# POWERAMP.net
KiCad netlist of a schematic drawn in Altium Designer
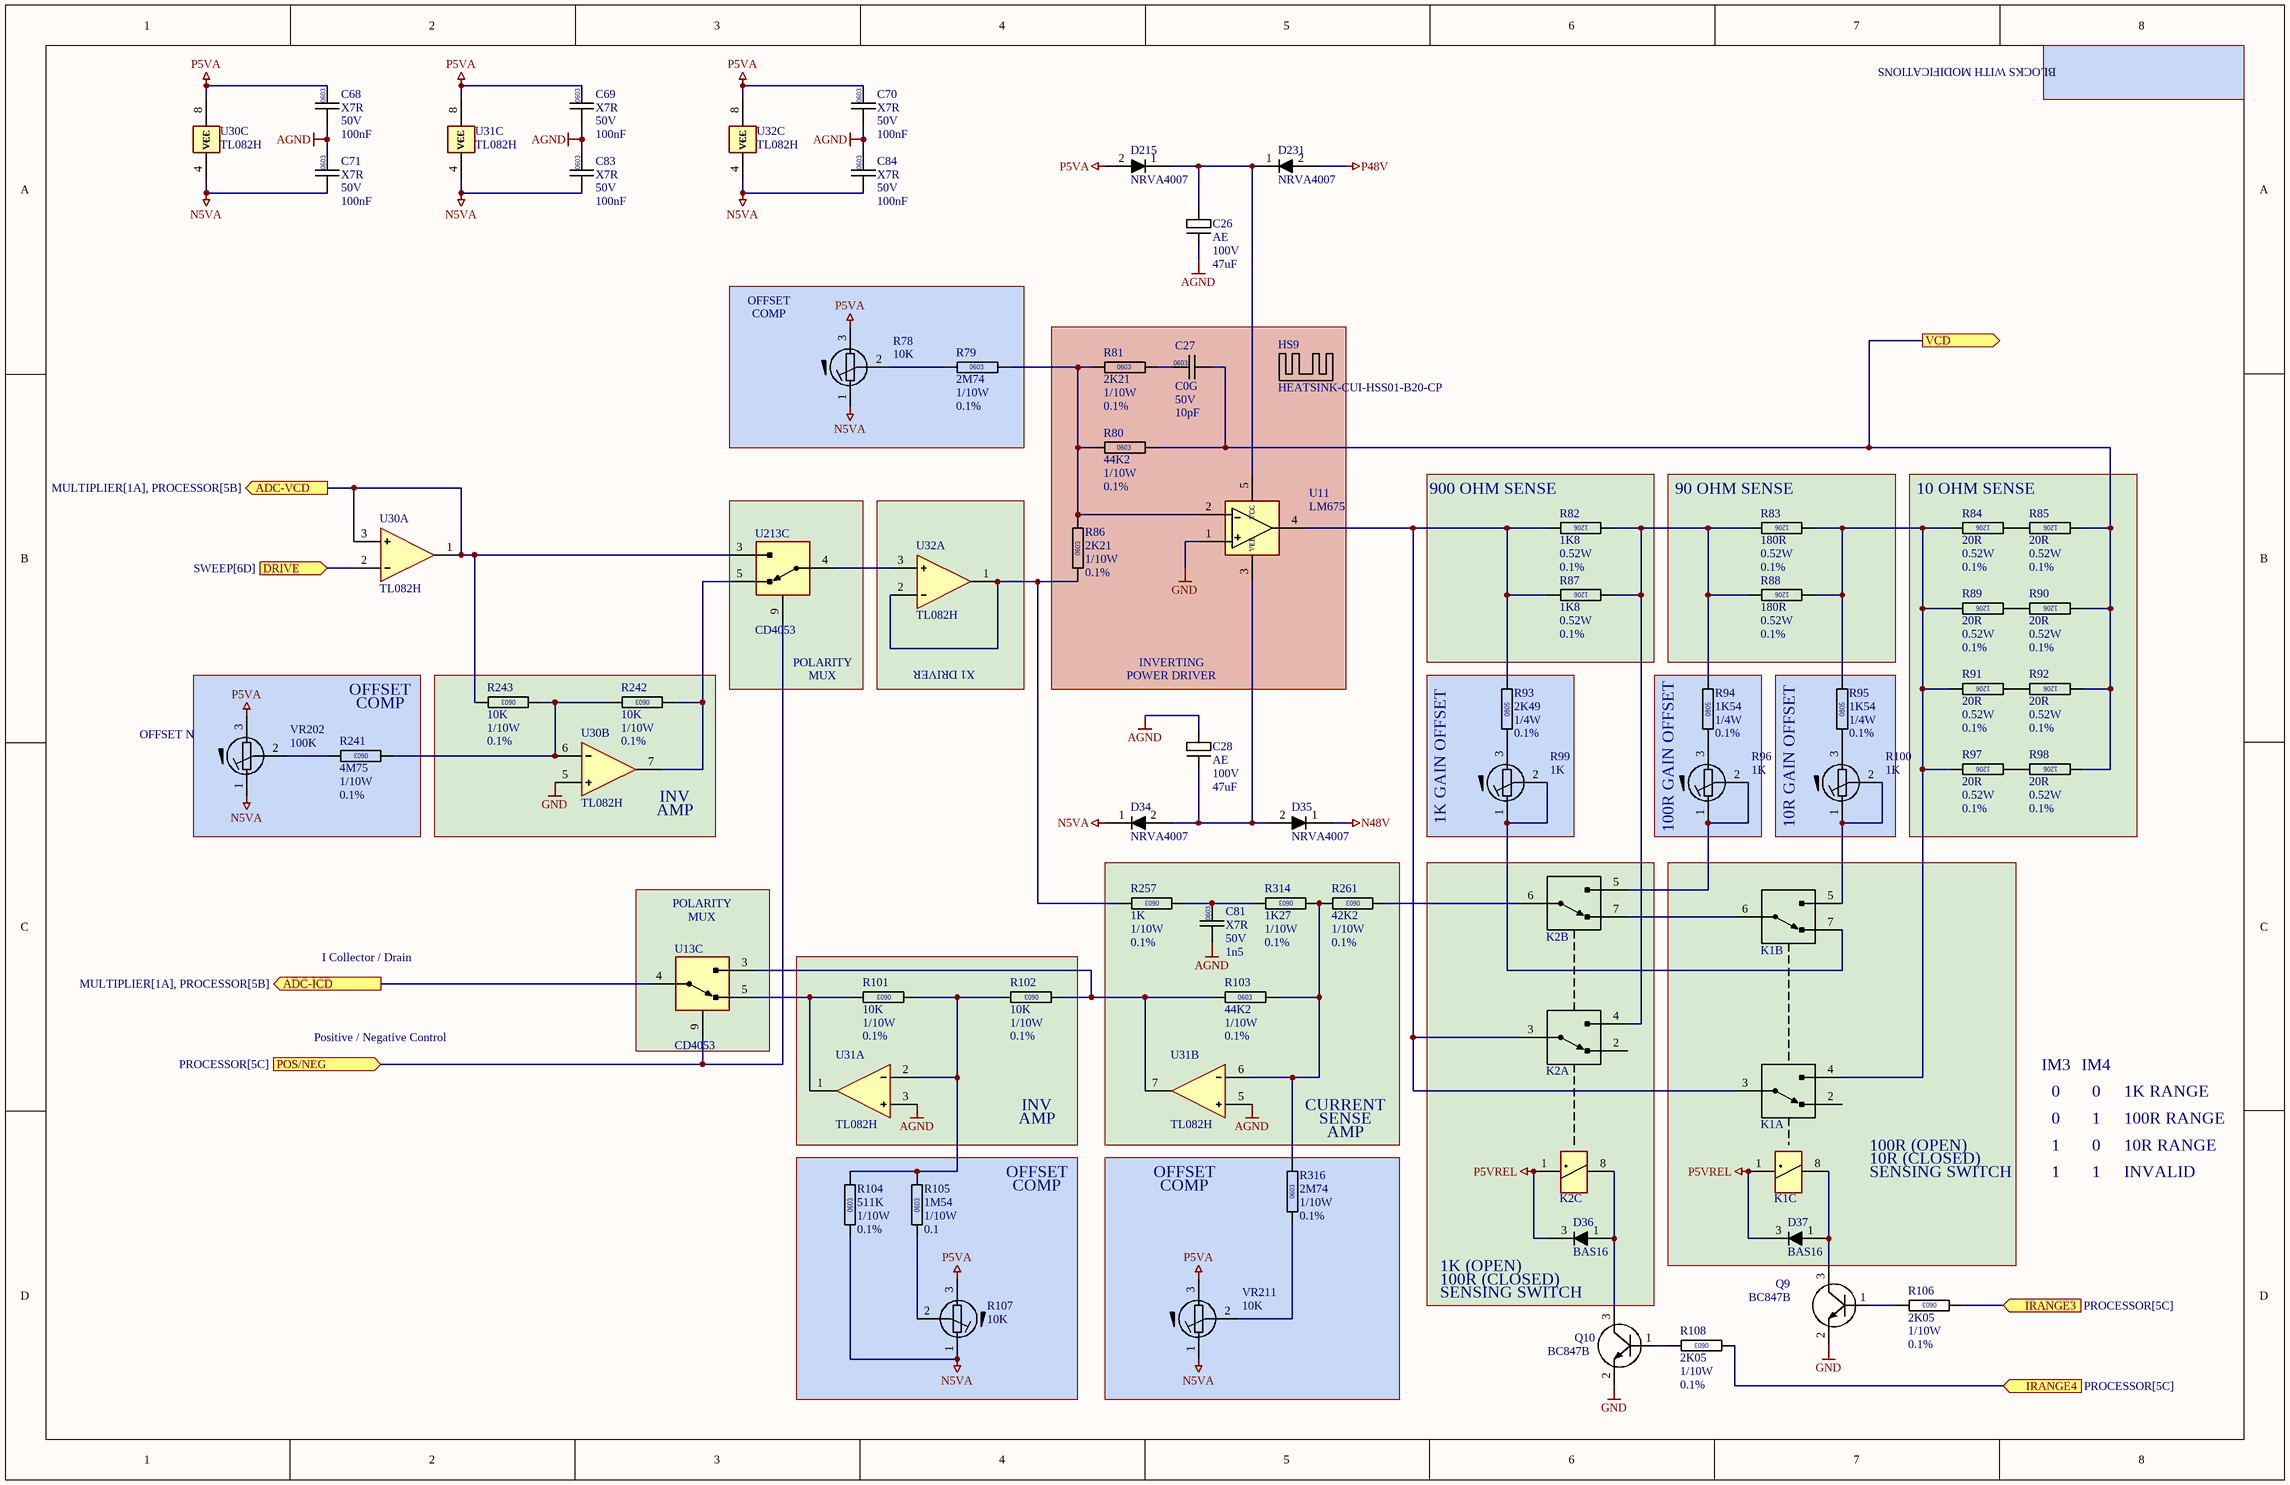
[diagram p0: POWERAMP.SchDoc]

(export (version "E")
  (design (tool "Eeschema 10.0.6"))
  (components
    (comp (ref "C26")
      (value "CAP0603")
      (footprint "CAPAE-KEMET-ESL476M100AH9AA")
      (description "CAPACITOR,ALU,47uF,100V,TH,P5mm,D10mm,H14mm")
      (fields
        (field (name "DIELECTRIC") "AE")
        (field (name "VOLTAGE") "100V")
        (field (name "CAPACITANCE") "47uF")
      )
      (libsource (lib "CAPACITORS") (part "CAPP-AE-47uF-100V-TH050P100D140H"))
    )
    (comp (ref "C27")
      (value "CAP0603")
      (footprint "CAPC0603")
      (description "CAPACITOR,CERAMIC,10pF,50V,C0G,0603")
      (fields
        (field (name "DIELECTRIC") "C0G")
        (field (name "VOLTAGE") "50V")
        (field (name "CAPACITANCE") "10pF")
      )
      (libsource (lib "CAPACITORS") (part "CAPC-0603-10PF-50V-C0G"))
    )
    (comp (ref "C28")
      (value "CAP0603")
      (footprint "CAPAE-KEMET-ESL476M100AH9AA")
      (description "CAPACITOR,ALU,47uF,100V,TH,P5mm,D10mm,H14mm")
      (fields
        (field (name "DIELECTRIC") "AE")
        (field (name "VOLTAGE") "100V")
        (field (name "CAPACITANCE") "47uF")
      )
      (libsource (lib "CAPACITORS") (part "CAPP-AE-47uF-100V-TH050P100D140H"))
    )
    (comp (ref "C68")
      (value "CAP0603")
      (footprint "CAPC0603")
      (description "CAPACITOR,CERAMIC,100nF,50V,X7R,0603")
      (fields
        (field (name "DIELECTRIC") "X7R")
        (field (name "VOLTAGE") "50V")
        (field (name "CAPACITANCE") "100nF")
      )
      (libsource (lib "CAPACITORS") (part "CAPC-0603-100nF-50V-X7R"))
    )
    (comp (ref "C69")
      (value "CAP0603")
      (footprint "CAPC0603")
      (description "CAPACITOR,CERAMIC,100nF,50V,X7R,0603")
      (fields
        (field (name "DIELECTRIC") "X7R")
        (field (name "VOLTAGE") "50V")
        (field (name "CAPACITANCE") "100nF")
      )
      (libsource (lib "CAPACITORS") (part "CAPC-0603-100nF-50V-X7R"))
    )
    (comp (ref "C70")
      (value "CAP0603")
      (footprint "CAPC0603")
      (description "CAPACITOR,CERAMIC,100nF,50V,X7R,0603")
      (fields
        (field (name "DIELECTRIC") "X7R")
        (field (name "VOLTAGE") "50V")
        (field (name "CAPACITANCE") "100nF")
      )
      (libsource (lib "CAPACITORS") (part "CAPC-0603-100nF-50V-X7R"))
    )
    (comp (ref "C71")
      (value "CAP0603")
      (footprint "CAPC0603")
      (description "CAPACITOR,CERAMIC,100nF,50V,X7R,0603")
      (fields
        (field (name "DIELECTRIC") "X7R")
        (field (name "VOLTAGE") "50V")
        (field (name "CAPACITANCE") "100nF")
      )
      (libsource (lib "CAPACITORS") (part "CAPC-0603-100nF-50V-X7R"))
    )
    (comp (ref "C81")
      (value "CAP0603")
      (footprint "CAPC0603")
      (description "CAPACITOR,CERAMIC,1n5,50V,X7R,0603")
      (fields
        (field (name "DIELECTRIC") "X7R")
        (field (name "VOLTAGE") "50V")
        (field (name "CAPACITANCE") "1n5")
      )
      (libsource (lib "CAPACITORS") (part "CAPC-0603-1n5-50V-X7R"))
    )
    (comp (ref "C83")
      (value "CAP0603")
      (footprint "CAPC0603")
      (description "CAPACITOR,CERAMIC,100nF,50V,X7R,0603")
      (fields
        (field (name "DIELECTRIC") "X7R")
        (field (name "VOLTAGE") "50V")
        (field (name "CAPACITANCE") "100nF")
      )
      (libsource (lib "CAPACITORS") (part "CAPC-0603-100nF-50V-X7R"))
    )
    (comp (ref "C84")
      (value "CAP0603")
      (footprint "CAPC0603")
      (description "CAPACITOR,CERAMIC,100nF,50V,X7R,0603")
      (fields
        (field (name "DIELECTRIC") "X7R")
        (field (name "VOLTAGE") "50V")
        (field (name "CAPACITANCE") "100nF")
      )
      (libsource (lib "CAPACITORS") (part "CAPC-0603-100nF-50V-X7R"))
    )
    (comp (ref "D34")
      (value "NRVA4007")
      (footprint "DO214AC")
      (description "DIODE,RECTIFIER,1000V,1A,ONSEMI,NRVA4007,SMA")
      (libsource (lib "DIODES") (part "DIODE-ONSEMI-NRVA4007T3G"))
    )
    (comp (ref "D35")
      (value "NRVA4007")
      (footprint "DO214AC")
      (description "DIODE,RECTIFIER,1000V,1A,ONSEMI,NRVA4007,SMA")
      (libsource (lib "DIODES") (part "DIODE-ONSEMI-NRVA4007T3G"))
    )
    (comp (ref "D36")
      (value "BAS16")
      (footprint "SOT23")
      (description "DIODE,RECTIFIER,75V,0.3A,BAS16,SOT23")
      (libsource (lib "DIODES") (part "DIODE-RECTIFIER-DIODES-BAS16-SOT23"))
    )
    (comp (ref "D37")
      (value "BAS16")
      (footprint "SOT23")
      (description "DIODE,RECTIFIER,75V,0.3A,BAS16,SOT23")
      (libsource (lib "DIODES") (part "DIODE-RECTIFIER-DIODES-BAS16-SOT23"))
    )
    (comp (ref "D215")
      (value "NRVA4007")
      (footprint "DO214AC")
      (description "DIODE,RECTIFIER,1000V,1A,ONSEMI,NRVA4007,SMA")
      (libsource (lib "DIODES") (part "DIODE-ONSEMI-NRVA4007T3G"))
    )
    (comp (ref "D231")
      (value "NRVA4007")
      (footprint "DO214AC")
      (description "DIODE,RECTIFIER,1000V,1A,ONSEMI,NRVA4007,SMA")
      (libsource (lib "DIODES") (part "DIODE-ONSEMI-NRVA4007T3G"))
    )
    (comp (ref "HS9")
      (value "HEATSINK-CUI-HSS01-B20-CP")
      (footprint "HEATSINK-CUI-HSS01-B20-CP")
      (description "HEATSINKSTAMPED,CLIP-ON,BOARDMOUNT,3W,25C/W,CUI,HSS01-B20-CP")
      (libsource (lib "HEATSINK") (part "HEATSINK-CUI-HSS01-B20-CP"))
    )
    (comp (ref "K1")
      (value "RELAY-KEMET-UA2-5NJ")
      (footprint "RELAY-KEMET-UA2-5NJ")
      (description "RELAY,DPDT,1A,250VAC,220VDC,5V COIL,KEMET,UA2-5NJ")
      (libsource (lib "RELAYS") (part "RELAY-KEMET-UA2-5NJ"))
    )
    (comp (ref "K2")
      (value "RELAY-KEMET-UA2-5NJ")
      (footprint "RELAY-KEMET-UA2-5NJ")
      (description "RELAY,DPDT,1A,250VAC,220VDC,5V COIL,KEMET,UA2-5NJ")
      (libsource (lib "") (part "RELAY-KEMET-UA2-5NJ_1"))
    )
    (comp (ref "Q9")
      (value "BC847B")
      (footprint "SOT23")
      (description "XSTR,NPN,45V,0.1A,,BC847B,SOT23")
      (libsource (lib "TRANSISTORS") (part "XSTR-NPN-BC847"))
    )
    (comp (ref "Q10")
      (value "BC847B")
      (footprint "SOT23")
      (description "XSTR,NPN,45V,0.1A,,BC847B,SOT23")
      (libsource (lib "TRANSISTORS") (part "XSTR-NPN-BC847"))
    )
    (comp (ref "R78")
      (value "10K")
      (footprint "TRIMMER-BOURNS-3214X")
      (description "RESISTOR,MULTITURN,VERTICAL,5T,10K")
      (fields (field (name "Comment") "TRIMMER-BOURNS-3214X-1-103E"))
      (libsource (lib "RESISTORS") (part "TRIMMER-BOURNS-3214X-1-103E"))
    )
    (comp (ref "R79")
      (value "2M74")
      (footprint "RESC0603")
      (description "RESISTOR,2M74,0.1%,100mW,0603 (1608)")
      (fields
        (field (name "POWER") "1/10W")
        (field (name "TOLERANCE") "0.1%")
        (field (name "Comment") "RESC0603")
      )
      (libsource (lib "RESISTORS") (part "RESC-0603-2M74-0.1%-1/10W"))
    )
    (comp (ref "R80")
      (value "44K2")
      (footprint "RESC0603")
      (description "RESISTOR,44K2,0.1%,100mW,0603 (1608)")
      (fields
        (field (name "POWER") "1/10W")
        (field (name "TOLERANCE") "0.1%")
        (field (name "Comment") "RESC0603")
      )
      (libsource (lib "RESISTORS") (part "RESC-0603-44K2-0.1%-1/10W"))
    )
    (comp (ref "R81")
      (value "2K21")
      (footprint "RESC0603")
      (description "RESISTOR,2K21,0.1%,100mW,0603 (1608)")
      (fields
        (field (name "POWER") "1/10W")
        (field (name "TOLERANCE") "0.1%")
        (field (name "Comment") "RESC0603")
      )
      (libsource (lib "RESISTORS") (part "RESC-0603-2K21-0.1%-1/10W"))
    )
    (comp (ref "R82")
      (value "1K8")
      (footprint "RESC1206")
      (description "RESISTOR,1K8,1206,0.1%,520mW,1206")
      (fields
        (field (name "POWER") "0.52W")
        (field (name "TOLERANCE") "0.1%")
        (field (name "Comment") "RESC1206")
      )
      (libsource (lib "RESISTORS") (part "RESC-1206-1K8-0.1%-1/2W"))
    )
    (comp (ref "R83")
      (value "180R")
      (footprint "RESC1206")
      (description "RESISTOR,180,1206,0.1%,520mW,1206")
      (fields
        (field (name "POWER") "0.52W")
        (field (name "TOLERANCE") "0.1%")
        (field (name "Comment") "RESC1206")
      )
      (libsource (lib "RESISTORS") (part "RESC-1206-180R-0.1%-1/2W"))
    )
    (comp (ref "R84")
      (value "20R")
      (footprint "RESC1206")
      (description "RESISTOR,20R,1206,0.1%,520mW,1206")
      (fields
        (field (name "POWER") "0.52W")
        (field (name "TOLERANCE") "0.1%")
        (field (name "Comment") "RESC1206")
      )
      (libsource (lib "RESISTORS") (part "RESC-1206-20R-0.1%-1/2W"))
    )
    (comp (ref "R85")
      (value "20R")
      (footprint "RESC1206")
      (description "RESISTOR,20R,1206,0.1%,520mW,1206")
      (fields
        (field (name "POWER") "0.52W")
        (field (name "TOLERANCE") "0.1%")
        (field (name "Comment") "RESC1206")
      )
      (libsource (lib "RESISTORS") (part "RESC-1206-20R-0.1%-1/2W"))
    )
    (comp (ref "R86")
      (value "2K21")
      (footprint "RESC0603")
      (description "RESISTOR,2K21,0.1%,100mW,0603 (1608)")
      (fields
        (field (name "POWER") "1/10W")
        (field (name "TOLERANCE") "0.1%")
        (field (name "Comment") "RESC0603")
      )
      (libsource (lib "RESISTORS") (part "RESC-0603-2K21-0.1%-1/10W"))
    )
    (comp (ref "R87")
      (value "1K8")
      (footprint "RESC1206")
      (description "RESISTOR,1K8,1206,0.1%,520mW,1206")
      (fields
        (field (name "POWER") "0.52W")
        (field (name "TOLERANCE") "0.1%")
        (field (name "Comment") "RESC1206")
      )
      (libsource (lib "RESISTORS") (part "RESC-1206-1K8-0.1%-1/2W"))
    )
    (comp (ref "R88")
      (value "180R")
      (footprint "RESC1206")
      (description "RESISTOR,180,1206,0.1%,520mW,1206")
      (fields
        (field (name "POWER") "0.52W")
        (field (name "TOLERANCE") "0.1%")
        (field (name "Comment") "RESC1206")
      )
      (libsource (lib "RESISTORS") (part "RESC-1206-180R-0.1%-1/2W"))
    )
    (comp (ref "R89")
      (value "20R")
      (footprint "RESC1206")
      (description "RESISTOR,20R,1206,0.1%,520mW,1206")
      (fields
        (field (name "POWER") "0.52W")
        (field (name "TOLERANCE") "0.1%")
        (field (name "Comment") "RESC1206")
      )
      (libsource (lib "RESISTORS") (part "RESC-1206-20R-0.1%-1/2W"))
    )
    (comp (ref "R90")
      (value "20R")
      (footprint "RESC1206")
      (description "RESISTOR,20R,1206,0.1%,520mW,1206")
      (fields
        (field (name "POWER") "0.52W")
        (field (name "TOLERANCE") "0.1%")
        (field (name "Comment") "RESC1206")
      )
      (libsource (lib "RESISTORS") (part "RESC-1206-20R-0.1%-1/2W"))
    )
    (comp (ref "R91")
      (value "20R")
      (footprint "RESC1206")
      (description "RESISTOR,20R,1206,0.1%,520mW,1206")
      (fields
        (field (name "POWER") "0.52W")
        (field (name "TOLERANCE") "0.1%")
        (field (name "Comment") "RESC1206")
      )
      (libsource (lib "RESISTORS") (part "RESC-1206-20R-0.1%-1/2W"))
    )
    (comp (ref "R92")
      (value "20R")
      (footprint "RESC1206")
      (description "RESISTOR,20R,1206,0.1%,520mW,1206")
      (fields
        (field (name "POWER") "0.52W")
        (field (name "TOLERANCE") "0.1%")
        (field (name "Comment") "RESC1206")
      )
      (libsource (lib "RESISTORS") (part "RESC-1206-20R-0.1%-1/2W"))
    )
    (comp (ref "R93")
      (value "2K49")
      (footprint "RESC0805")
      (description "RESISTOR,2K49,0.1%,250mW,0805")
      (fields
        (field (name "POWER") "1/4W")
        (field (name "TOLERANCE") "0.1%")
        (field (name "Comment") "RESC0805")
      )
      (libsource (lib "RESISTORS") (part "RESC-0805-2K49-0.1%-1/4W"))
    )
    (comp (ref "R94")
      (value "1K54")
      (footprint "RESC0805")
      (description "RESISTOR,1K54,0.1%,250mW,0805")
      (fields
        (field (name "POWER") "1/4W")
        (field (name "TOLERANCE") "0.1%")
        (field (name "Comment") "RESC0805")
      )
      (libsource (lib "RESISTORS") (part "RESC-0805-1K54-0.1%-1/4W"))
    )
    (comp (ref "R95")
      (value "1K54")
      (footprint "RESC0805")
      (description "RESISTOR,1K54,0.1%,250mW,0805")
      (fields
        (field (name "POWER") "1/4W")
        (field (name "TOLERANCE") "0.1%")
        (field (name "Comment") "RESC0805")
      )
      (libsource (lib "RESISTORS") (part "RESC-0805-1K54-0.1%-1/4W"))
    )
    (comp (ref "R96")
      (value "1K")
      (footprint "TRIMMER-BOURNS-3214X")
      (description "RESISTOR,MULTITURN,VERTICAL,5T,1K")
      (fields (field (name "Comment") "TRIMMER-BOURNS-3214X-1-102E"))
      (libsource (lib "RESISTORS") (part "TRIMMER-BOURNS-3214X-1-102E"))
    )
    (comp (ref "R97")
      (value "20R")
      (footprint "RESC1206")
      (description "RESISTOR,20R,1206,0.1%,520mW,1206")
      (fields
        (field (name "POWER") "0.52W")
        (field (name "TOLERANCE") "0.1%")
        (field (name "Comment") "RESC1206")
      )
      (libsource (lib "RESISTORS") (part "RESC-1206-20R-0.1%-1/2W"))
    )
    (comp (ref "R98")
      (value "20R")
      (footprint "RESC1206")
      (description "RESISTOR,20R,1206,0.1%,520mW,1206")
      (fields
        (field (name "POWER") "0.52W")
        (field (name "TOLERANCE") "0.1%")
        (field (name "Comment") "RESC1206")
      )
      (libsource (lib "RESISTORS") (part "RESC-1206-20R-0.1%-1/2W"))
    )
    (comp (ref "R99")
      (value "1K")
      (footprint "TRIMMER-BOURNS-3214X")
      (description "RESISTOR,MULTITURN,VERTICAL,5T,1K")
      (fields (field (name "Comment") "TRIMMER-BOURNS-3214X-1-102E"))
      (libsource (lib "RESISTORS") (part "TRIMMER-BOURNS-3214X-1-102E"))
    )
    (comp (ref "R100")
      (value "1K")
      (footprint "TRIMMER-BOURNS-3214X")
      (description "RESISTOR,MULTITURN,VERTICAL,5T,1K")
      (fields (field (name "Comment") "TRIMMER-BOURNS-3214X-1-102E"))
      (libsource (lib "RESISTORS") (part "TRIMMER-BOURNS-3214X-1-102E"))
    )
    (comp (ref "R101")
      (value "10K")
      (footprint "RESC0603")
      (description "RESISTOR,10K,0.1%,100mW,0603 (1608)")
      (fields
        (field (name "POWER") "1/10W")
        (field (name "TOLERANCE") "0.1%")
        (field (name "Comment") "RESC0603")
      )
      (libsource (lib "RESISTORS") (part "RESC-0603-10K-0.1%-1/10W"))
    )
    (comp (ref "R102")
      (value "10K")
      (footprint "RESC0603")
      (description "RESISTOR,10K,0.1%,100mW,0603 (1608)")
      (fields
        (field (name "POWER") "1/10W")
        (field (name "TOLERANCE") "0.1%")
        (field (name "Comment") "RESC0603")
      )
      (libsource (lib "RESISTORS") (part "RESC-0603-10K-0.1%-1/10W"))
    )
    (comp (ref "R103")
      (value "44K2")
      (footprint "RESC0603")
      (description "RESISTOR,44K2,0.1%,100mW,0603 (1608)")
      (fields
        (field (name "POWER") "1/10W")
        (field (name "TOLERANCE") "0.1%")
        (field (name "Comment") "RESC0603")
      )
      (libsource (lib "RESISTORS") (part "RESC-0603-44K2-0.1%-1/10W"))
    )
    (comp (ref "R104")
      (value "511K")
      (footprint "RESC0603")
      (description "RESISTOR,511K,0.1%,100mW,0603 (1608)")
      (fields
        (field (name "POWER") "1/10W")
        (field (name "TOLERANCE") "0.1%")
        (field (name "Comment") "RESC0603")
      )
      (libsource (lib "RESISTORS") (part "RESC-0603-511K-0.1%-1/10W"))
    )
    (comp (ref "R105")
      (value "1M54")
      (footprint "RESC0603")
      (description "RESISTOR,1M54,0.1%,100mW,0603 (1608)")
      (fields
        (field (name "POWER") "1/10W")
        (field (name "TOLERANCE") "0.1")
        (field (name "Comment") "RESC0603")
      )
      (libsource (lib "RESISTORS") (part "RESC-0603-1M54-0.1%-1/10W"))
    )
    (comp (ref "R106")
      (value "2K05")
      (footprint "RESC0603")
      (description "RESISTOR,2K05,0.11%,100mW,0603 (1608)")
      (fields
        (field (name "POWER") "1/10W")
        (field (name "TOLERANCE") "0.1%")
        (field (name "Comment") "RESC0603")
      )
      (libsource (lib "RESISTORS") (part "RESC-0603-2K05-0.1%-1/10W"))
    )
    (comp (ref "R107")
      (value "10K")
      (footprint "TRIMMER-BOURNS-3214X")
      (description "RESISTOR,MULTITURN,VERTICAL,5T,10K")
      (fields (field (name "Comment") "TRIMMER-BOURNS-3214X-1-103E"))
      (libsource (lib "RESISTORS") (part "TRIMMER-BOURNS-3214X-1-103E"))
    )
    (comp (ref "R108")
      (value "2K05")
      (footprint "RESC0603")
      (description "RESISTOR,2K05,0.11%,100mW,0603 (1608)")
      (fields
        (field (name "POWER") "1/10W")
        (field (name "TOLERANCE") "0.1%")
        (field (name "Comment") "RESC0603")
      )
      (libsource (lib "RESISTORS") (part "RESC-0603-2K05-0.1%-1/10W"))
    )
    (comp (ref "R241")
      (value "4M75")
      (footprint "RESC0603")
      (description "RESISTOR,4M75,0.1%,100mW,0603 (1608)")
      (fields
        (field (name "POWER") "1/10W")
        (field (name "TOLERANCE") "0.1%")
        (field (name "Comment") "RESC0603")
      )
      (libsource (lib "RESISTORS") (part "RESC-0603-4M75-1%-1/10W"))
    )
    (comp (ref "R242")
      (value "10K")
      (footprint "RESC0603")
      (description "RESISTOR,10K,0.1%,100mW,0603 (1608)")
      (fields
        (field (name "POWER") "1/10W")
        (field (name "TOLERANCE") "0.1%")
        (field (name "Comment") "RESC0603")
      )
      (libsource (lib "RESISTORS") (part "RESC-0603-10K-0.1%-1/10W"))
    )
    (comp (ref "R243")
      (value "10K")
      (footprint "RESC0603")
      (description "RESISTOR,10K,0.1%,100mW,0603 (1608)")
      (fields
        (field (name "POWER") "1/10W")
        (field (name "TOLERANCE") "0.1%")
        (field (name "Comment") "RESC0603")
      )
      (libsource (lib "RESISTORS") (part "RESC-0603-10K-0.1%-1/10W"))
    )
    (comp (ref "R257")
      (value "1K")
      (footprint "RESC0603")
      (description "RESISTOR,1K,0.1%,100mW,0603 (1608)")
      (fields
        (field (name "POWER") "1/10W")
        (field (name "TOLERANCE") "0.1%")
        (field (name "Comment") "RESC0603")
      )
      (libsource (lib "RESISTORS") (part "RESC-0603-1K-0.1%-1/10W"))
    )
    (comp (ref "R261")
      (value "42K2")
      (footprint "RESC0603")
      (description "RESISTOR,42K2,0.1%,100mW,0603 (1608)")
      (fields
        (field (name "POWER") "1/10W")
        (field (name "TOLERANCE") "0.1%")
        (field (name "Comment") "RESC0603")
      )
      (libsource (lib "RESISTORS") (part "RESC-0603-42K2-0.1%-1/10W"))
    )
    (comp (ref "R314")
      (value "1K27")
      (footprint "RESC0603")
      (description "RESISTOR,1K27,0.1%,100mW,0603 (1608)")
      (fields
        (field (name "POWER") "1/10W")
        (field (name "TOLERANCE") "0.1%")
        (field (name "Comment") "RESC0603")
      )
      (libsource (lib "RESISTORS") (part "RESC-0603-1K27-0.1%-1/10W"))
    )
    (comp (ref "R316")
      (value "2M74")
      (footprint "RESC0603")
      (description "RESISTOR,2M74,0.1%,100mW,0603 (1608)")
      (fields
        (field (name "POWER") "1/10W")
        (field (name "TOLERANCE") "0.1%")
        (field (name "Comment") "RESC0603")
      )
      (libsource (lib "RESISTORS") (part "RESC-0603-2M74-0.1%-1/10W"))
    )
    (comp (ref "U11")
      (value "LM675")
      (footprint "TO220-5-V")
      (description "IC,OPAMP,SINGLE,POWER,LM675,TO220-5")
      (libsource (lib "IC-OPAMP") (part "IC-TI-LM675-TO220-5"))
    )
    (comp (ref "U13")
      (value "CD4053")
      (footprint "SO127P600-16N")
      (description "IC,LOGIC,CMOS,4XXX,TRIPLE 2:1 MUX,SPLIT BLOCKS")
      (libsource (lib "IC-4XXX") (part "IC-TI-CD4053-SPLIT"))
    )
    (comp (ref "U30")
      (value "TL082H")
      (footprint "SO127P600-8N")
      (description "IC,OPAMP JFET,DUAL,TL082HIDR,SO8")
      (libsource (lib "IC-OPAMP") (part "IC-TI-TL082H-SO8"))
    )
    (comp (ref "U31")
      (value "TL082H")
      (footprint "SO127P600-8N")
      (description "IC,OPAMP JFET,DUAL,TL082HIDR,SO8")
      (libsource (lib "") (part "IC-TI-TL082H-SO8_1"))
    )
    (comp (ref "U32")
      (value "TL082H")
      (footprint "SO127P600-8N")
      (description "IC,OPAMP JFET,DUAL,TL082HIDR,SO8")
      (libsource (lib "") (part "IC-TI-TL082H-SO8_2"))
    )
    (comp (ref "U213")
      (value "CD4053")
      (footprint "SO127P600-16N")
      (description "IC,LOGIC,CMOS,4XXX,TRIPLE 2:1 MUX,SPLIT BLOCKS")
      (libsource (lib "") (part "IC-TI-CD4053-SPLIT_1"))
    )
    (comp (ref "VR202")
      (value "100K")
      (footprint "TRIMMER-BOURNS-3214X")
      (description "RESISTOR,MULTITURN,VERTICAL,5T,100K")
      (fields (field (name "Comment") "TRIMMER-BOURNS-3214X-1-104"))
      (libsource (lib "RESISTORS") (part "TRIMMER-BOURNS-3214X-1-104"))
    )
    (comp (ref "VR211")
      (value "10K")
      (footprint "TRIMMER-BOURNS-3214X")
      (description "RESISTOR,MULTITURN,VERTICAL,5T,10K")
      (fields (field (name "Comment") "TRIMMER-BOURNS-3214X-1-103E"))
      (libsource (lib "RESISTORS") (part "TRIMMER-BOURNS-3214X-1-103E"))
    )
  )
  (nets
    (net (code "1") (name "/ADC-ICD") (class "Default")
      (node (ref "U13") (pin "4") (pinfunction "Y3_4") (pintype "passive"))
    )
    (net (code "2") (name "/ADC-VCD") (class "Default")
      (node (ref "R243") (pin "1") (pintype "passive"))
      (node (ref "U213") (pin "3") (pinfunction "Y_3") (pintype "passive"))
      (node (ref "U30") (pin "1") (pinfunction "O_1") (pintype "passive"))
      (node (ref "U30") (pin "3") (pinfunction "+_3") (pintype "passive"))
    )
    (net (code "3") (name "/DRIVE") (class "Default")
      (node (ref "U30") (pin "2") (pinfunction "-_2") (pintype "passive"))
    )
    (net (code "4") (name "/IRANGE3") (class "Default") (node (ref "R106") (pin "1") (pintype "passive")))
    (net (code "5") (name "/IRANGE4") (class "Default") (node (ref "R108") (pin "1") (pintype "passive")))
    (net (code "6") (name "/POS{slash}NEG") (class "Default")
      (node (ref "U13") (pin "9") (pinfunction "B_9") (pintype "passive"))
      (node (ref "U213") (pin "9") (pinfunction "B_9") (pintype "passive"))
    )
    (net (code "7") (name "/VCD") (class "Default")
      (node (ref "C27") (pin "2") (pintype "passive"))
      (node (ref "R80") (pin "2") (pintype "passive"))
      (node (ref "R85") (pin "2") (pintype "passive"))
      (node (ref "R90") (pin "2") (pintype "passive"))
      (node (ref "R92") (pin "2") (pintype "passive"))
      (node (ref "R98") (pin "2") (pintype "passive"))
    )
    (net (code "8") (name "AGND") (class "Default")
      (node (ref "C26") (pin "2") (pintype "passive"))
      (node (ref "C28") (pin "1") (pintype "passive"))
      (node (ref "C68") (pin "2") (pintype "passive"))
      (node (ref "C69") (pin "2") (pintype "passive"))
      (node (ref "C70") (pin "2") (pintype "passive"))
      (node (ref "C71") (pin "1") (pintype "passive"))
      (node (ref "C81") (pin "2") (pintype "passive"))
      (node (ref "C83") (pin "1") (pintype "passive"))
      (node (ref "C84") (pin "1") (pintype "passive"))
      (node (ref "U31") (pin "3") (pinfunction "+_3") (pintype "passive"))
      (node (ref "U31") (pin "5") (pinfunction "+_5") (pintype "passive"))
    )
    (net (code "9") (name "GND") (class "Default")
      (node (ref "Q10") (pin "2") (pinfunction "E_2") (pintype "passive"))
      (node (ref "Q9") (pin "2") (pinfunction "E_2") (pintype "passive"))
      (node (ref "U11") (pin "1") (pinfunction "+_1") (pintype "passive"))
      (node (ref "U30") (pin "5") (pinfunction "+_5") (pintype "passive"))
    )
    (net (code "10") (name "N5VA") (class "Default")
      (node (ref "C71") (pin "2") (pintype "passive"))
      (node (ref "C83") (pin "2") (pintype "passive"))
      (node (ref "C84") (pin "2") (pintype "passive"))
      (node (ref "D34") (pin "1") (pinfunction "K_1") (pintype "passive"))
      (node (ref "R104") (pin "2") (pintype "passive"))
      (node (ref "R107") (pin "1") (pinfunction "1_1") (pintype "passive"))
      (node (ref "R78") (pin "1") (pinfunction "1_1") (pintype "passive"))
      (node (ref "U30") (pin "4") (pinfunction "VEE_4") (pintype "passive"))
      (node (ref "U31") (pin "4") (pinfunction "VEE_4") (pintype "passive"))
      (node (ref "U32") (pin "4") (pinfunction "VEE_4") (pintype "passive"))
      (node (ref "VR202") (pin "1") (pinfunction "1_1") (pintype "passive"))
      (node (ref "VR211") (pin "1") (pinfunction "1_1") (pintype "passive"))
    )
    (net (code "11") (name "N48V") (class "Default")
      (node (ref "D35") (pin "1") (pinfunction "K_1") (pintype "passive"))
    )
    (net (code "12") (name "Net-(C27-Pad1)") (class "Default")
      (node (ref "C27") (pin "1") (pintype "passive"))
      (node (ref "R81") (pin "2") (pintype "passive"))
    )
    (net (code "13") (name "Net-(C81-Pad1)") (class "Default")
      (node (ref "C81") (pin "1") (pintype "passive"))
      (node (ref "R257") (pin "2") (pintype "passive"))
      (node (ref "R314") (pin "1") (pintype "passive"))
    )
    (net (code "14") (name "Net-(D34-A)") (class "Default")
      (node (ref "C28") (pin "2") (pintype "passive"))
      (node (ref "D34") (pin "2") (pinfunction "A_2") (pintype "passive"))
      (node (ref "D35") (pin "2") (pinfunction "A_2") (pintype "passive"))
      (node (ref "U11") (pin "3") (pinfunction "VEE_3") (pintype "passive"))
    )
    (net (code "15") (name "Net-(D36-A)") (class "Default")
      (node (ref "D36") (pin "1") (pinfunction "A_1") (pintype "passive"))
      (node (ref "K2") (pin "8") (pinfunction "8_8") (pintype "passive"))
      (node (ref "Q10") (pin "3") (pinfunction "C_3") (pintype "passive"))
    )
    (net (code "16") (name "Net-(D37-A)") (class "Default")
      (node (ref "D37") (pin "1") (pinfunction "A_1") (pintype "passive"))
      (node (ref "K1") (pin "8") (pinfunction "8_8") (pintype "passive"))
      (node (ref "Q9") (pin "3") (pinfunction "C_3") (pintype "passive"))
    )
    (net (code "17") (name "Net-(D215-K)") (class "Default")
      (node (ref "C26") (pin "1") (pintype "passive"))
      (node (ref "D215") (pin "1") (pinfunction "K_1") (pintype "passive"))
      (node (ref "D231") (pin "1") (pinfunction "K_1") (pintype "passive"))
      (node (ref "U11") (pin "5") (pinfunction "VCC_5") (pintype "passive"))
    )
    (net (code "18") (name "Net-(K1A-COM)") (class "Default")
      (node (ref "K1") (pin "3") (pinfunction "COM_3") (pintype "passive"))
      (node (ref "K2") (pin "3") (pinfunction "COM_3") (pintype "passive"))
      (node (ref "R82") (pin "1") (pintype "passive"))
      (node (ref "R87") (pin "1") (pintype "passive"))
      (node (ref "R93") (pin "1") (pintype "passive"))
      (node (ref "U11") (pin "4") (pinfunction "OUT_4") (pintype "passive"))
    )
    (net (code "19") (name "Net-(K1A-NO)") (class "Default")
      (node (ref "K1") (pin "4") (pinfunction "NO_4") (pintype "passive"))
      (node (ref "R83") (pin "2") (pintype "passive"))
      (node (ref "R84") (pin "1") (pintype "passive"))
      (node (ref "R88") (pin "2") (pintype "passive"))
      (node (ref "R89") (pin "1") (pintype "passive"))
      (node (ref "R91") (pin "1") (pintype "passive"))
      (node (ref "R95") (pin "2") (pintype "passive"))
      (node (ref "R97") (pin "1") (pintype "passive"))
    )
    (net (code "20") (name "Net-(K1B-COM)") (class "Default")
      (node (ref "K1") (pin "6") (pinfunction "COM_6") (pintype "passive"))
      (node (ref "K2") (pin "7") (pinfunction "NC_7") (pintype "passive"))
    )
    (net (code "21") (name "Net-(K1B-NC)") (class "Default")
      (node (ref "K1") (pin "7") (pinfunction "NC_7") (pintype "passive"))
      (node (ref "R99") (pin "1") (pinfunction "1_1") (pintype "passive"))
      (node (ref "R99") (pin "2") (pinfunction "2_2") (pintype "passive"))
    )
    (net (code "22") (name "Net-(K1B-NO)") (class "Default")
      (node (ref "K1") (pin "5") (pinfunction "NO_5") (pintype "passive"))
      (node (ref "R100") (pin "1") (pinfunction "1_1") (pintype "passive"))
      (node (ref "R100") (pin "2") (pinfunction "2_2") (pintype "passive"))
    )
    (net (code "23") (name "Net-(K2A-NO)") (class "Default")
      (node (ref "K2") (pin "4") (pinfunction "NO_4") (pintype "passive"))
      (node (ref "R82") (pin "2") (pintype "passive"))
      (node (ref "R83") (pin "1") (pintype "passive"))
      (node (ref "R87") (pin "2") (pintype "passive"))
      (node (ref "R88") (pin "1") (pintype "passive"))
      (node (ref "R94") (pin "2") (pintype "passive"))
    )
    (net (code "24") (name "Net-(K2B-COM)") (class "Default")
      (node (ref "K2") (pin "6") (pinfunction "COM_6") (pintype "passive"))
      (node (ref "R261") (pin "2") (pintype "passive"))
    )
    (net (code "25") (name "Net-(K2B-NO)") (class "Default")
      (node (ref "K2") (pin "5") (pinfunction "NO_5") (pintype "passive"))
      (node (ref "R96") (pin "1") (pinfunction "1_1") (pintype "passive"))
      (node (ref "R96") (pin "2") (pinfunction "2_2") (pintype "passive"))
    )
    (net (code "26") (name "Net-(Q9-B)") (class "Default")
      (node (ref "Q9") (pin "1") (pinfunction "B_1") (pintype "passive"))
      (node (ref "R106") (pin "2") (pintype "passive"))
    )
    (net (code "27") (name "Net-(Q10-B)") (class "Default")
      (node (ref "Q10") (pin "1") (pinfunction "B_1") (pintype "passive"))
      (node (ref "R108") (pin "2") (pintype "passive"))
    )
    (net (code "28") (name "Net-(R78-Pad2)") (class "Default")
      (node (ref "R78") (pin "2") (pinfunction "2_2") (pintype "passive"))
      (node (ref "R79") (pin "1") (pintype "passive"))
    )
    (net (code "29") (name "Net-(R84-Pad2)") (class "Default")
      (node (ref "R84") (pin "2") (pintype "passive"))
      (node (ref "R85") (pin "1") (pintype "passive"))
    )
    (net (code "30") (name "Net-(R89-Pad2)") (class "Default")
      (node (ref "R89") (pin "2") (pintype "passive"))
      (node (ref "R90") (pin "1") (pintype "passive"))
    )
    (net (code "31") (name "Net-(R91-Pad2)") (class "Default")
      (node (ref "R91") (pin "2") (pintype "passive"))
      (node (ref "R92") (pin "1") (pintype "passive"))
    )
    (net (code "32") (name "Net-(R93-Pad2)") (class "Default")
      (node (ref "R93") (pin "2") (pintype "passive"))
      (node (ref "R99") (pin "3") (pinfunction "3_3") (pintype "passive"))
    )
    (net (code "33") (name "Net-(R94-Pad1)") (class "Default")
      (node (ref "R94") (pin "1") (pintype "passive"))
      (node (ref "R96") (pin "3") (pinfunction "3_3") (pintype "passive"))
    )
    (net (code "34") (name "Net-(R97-Pad2)") (class "Default")
      (node (ref "R97") (pin "2") (pintype "passive"))
      (node (ref "R98") (pin "1") (pintype "passive"))
    )
    (net (code "35") (name "Net-(R100-Pad3)") (class "Default")
      (node (ref "R100") (pin "3") (pinfunction "3_3") (pintype "passive"))
      (node (ref "R95") (pin "1") (pintype "passive"))
    )
    (net (code "36") (name "Net-(R105-Pad2)") (class "Default")
      (node (ref "R105") (pin "2") (pintype "passive"))
      (node (ref "R107") (pin "2") (pinfunction "2_2") (pintype "passive"))
    )
    (net (code "37") (name "Net-(R241-Pad1)") (class "Default")
      (node (ref "R241") (pin "1") (pintype "passive"))
      (node (ref "VR202") (pin "2") (pinfunction "2_2") (pintype "passive"))
    )
    (net (code "38") (name "Net-(R316-Pad1)") (class "Default")
      (node (ref "R316") (pin "1") (pintype "passive"))
      (node (ref "VR211") (pin "2") (pinfunction "2_2") (pintype "passive"))
    )
    (net (code "39") (name "Net-(U11--)") (class "Default")
      (node (ref "R79") (pin "2") (pintype "passive"))
      (node (ref "R80") (pin "1") (pintype "passive"))
      (node (ref "R81") (pin "1") (pintype "passive"))
      (node (ref "R86") (pin "2") (pintype "passive"))
      (node (ref "U11") (pin "2") (pinfunction "-_2") (pintype "passive"))
    )
    (net (code "40") (name "Net-(U13C-Y)") (class "Default")
      (node (ref "R102") (pin "2") (pintype "passive"))
      (node (ref "R103") (pin "1") (pintype "passive"))
      (node (ref "U13") (pin "3") (pinfunction "Y_3") (pintype "passive"))
      (node (ref "U31") (pin "7") (pinfunction "O_7") (pintype "passive"))
    )
    (net (code "41") (name "Net-(U13C-Y1)") (class "Default")
      (node (ref "R101") (pin "1") (pintype "passive"))
      (node (ref "U13") (pin "5") (pinfunction "Y1_5") (pintype "passive"))
      (node (ref "U31") (pin "1") (pinfunction "O_1") (pintype "passive"))
    )
    (net (code "42") (name "Net-(U30B--)") (class "Default")
      (node (ref "R241") (pin "2") (pintype "passive"))
      (node (ref "R242") (pin "1") (pintype "passive"))
      (node (ref "R243") (pin "2") (pintype "passive"))
      (node (ref "U30") (pin "6") (pinfunction "-_6") (pintype "passive"))
    )
    (net (code "43") (name "Net-(U31A--)") (class "Default")
      (node (ref "R101") (pin "2") (pintype "passive"))
      (node (ref "R102") (pin "1") (pintype "passive"))
      (node (ref "R104") (pin "1") (pintype "passive"))
      (node (ref "R105") (pin "1") (pintype "passive"))
      (node (ref "U31") (pin "2") (pinfunction "-_2") (pintype "passive"))
    )
    (net (code "44") (name "Net-(U31B--)") (class "Default")
      (node (ref "R103") (pin "2") (pintype "passive"))
      (node (ref "R261") (pin "1") (pintype "passive"))
      (node (ref "R314") (pin "2") (pintype "passive"))
      (node (ref "R316") (pin "2") (pintype "passive"))
      (node (ref "U31") (pin "6") (pinfunction "-_6") (pintype "passive"))
    )
    (net (code "45") (name "Net-(U32A--)") (class "Default")
      (node (ref "R257") (pin "1") (pintype "passive"))
      (node (ref "R86") (pin "1") (pintype "passive"))
      (node (ref "U32") (pin "1") (pinfunction "O_1") (pintype "passive"))
      (node (ref "U32") (pin "2") (pinfunction "-_2") (pintype "passive"))
    )
    (net (code "46") (name "Net-(U213C-Y1)") (class "Default")
      (node (ref "R242") (pin "2") (pintype "passive"))
      (node (ref "U213") (pin "5") (pinfunction "Y1_5") (pintype "passive"))
      (node (ref "U30") (pin "7") (pinfunction "O_7") (pintype "passive"))
    )
    (net (code "47") (name "Net-(U213C-Y3)") (class "Default")
      (node (ref "U213") (pin "4") (pinfunction "Y3_4") (pintype "passive"))
      (node (ref "U32") (pin "3") (pinfunction "+_3") (pintype "passive"))
    )
    (net (code "48") (name "P5VA") (class "Default")
      (node (ref "C68") (pin "1") (pintype "passive"))
      (node (ref "C69") (pin "1") (pintype "passive"))
      (node (ref "C70") (pin "1") (pintype "passive"))
      (node (ref "D215") (pin "2") (pinfunction "A_2") (pintype "passive"))
      (node (ref "R107") (pin "3") (pinfunction "3_3") (pintype "passive"))
      (node (ref "R78") (pin "3") (pinfunction "3_3") (pintype "passive"))
      (node (ref "U30") (pin "8") (pinfunction "VCC_8") (pintype "passive"))
      (node (ref "U31") (pin "8") (pinfunction "VCC_8") (pintype "passive"))
      (node (ref "U32") (pin "8") (pinfunction "VCC_8") (pintype "passive"))
      (node (ref "VR202") (pin "3") (pinfunction "3_3") (pintype "passive"))
      (node (ref "VR211") (pin "3") (pinfunction "3_3") (pintype "passive"))
    )
    (net (code "49") (name "P5VREL") (class "Default")
      (node (ref "D36") (pin "3") (pinfunction "K_3") (pintype "passive"))
      (node (ref "D37") (pin "3") (pinfunction "K_3") (pintype "passive"))
      (node (ref "K1") (pin "1") (pinfunction "1_1") (pintype "passive"))
      (node (ref "K2") (pin "1") (pinfunction "1_1") (pintype "passive"))
    )
    (net (code "50") (name "P48V") (class "Default")
      (node (ref "D231") (pin "2") (pinfunction "A_2") (pintype "passive"))
    )
    (net (code "51") (name "unconnected-(K1A-NC-Pad2)") (class "Default")
      (node (ref "K1") (pin "2") (pinfunction "NC_2") (pintype "passive"))
    )
    (net (code "52") (name "unconnected-(K2A-NC-Pad2)") (class "Default")
      (node (ref "K2") (pin "2") (pinfunction "NC_2") (pintype "passive"))
    )
  )
)
